# MAIN_SPACER_2.net
KiCad netlist of a schematic drawn in Altium Designer
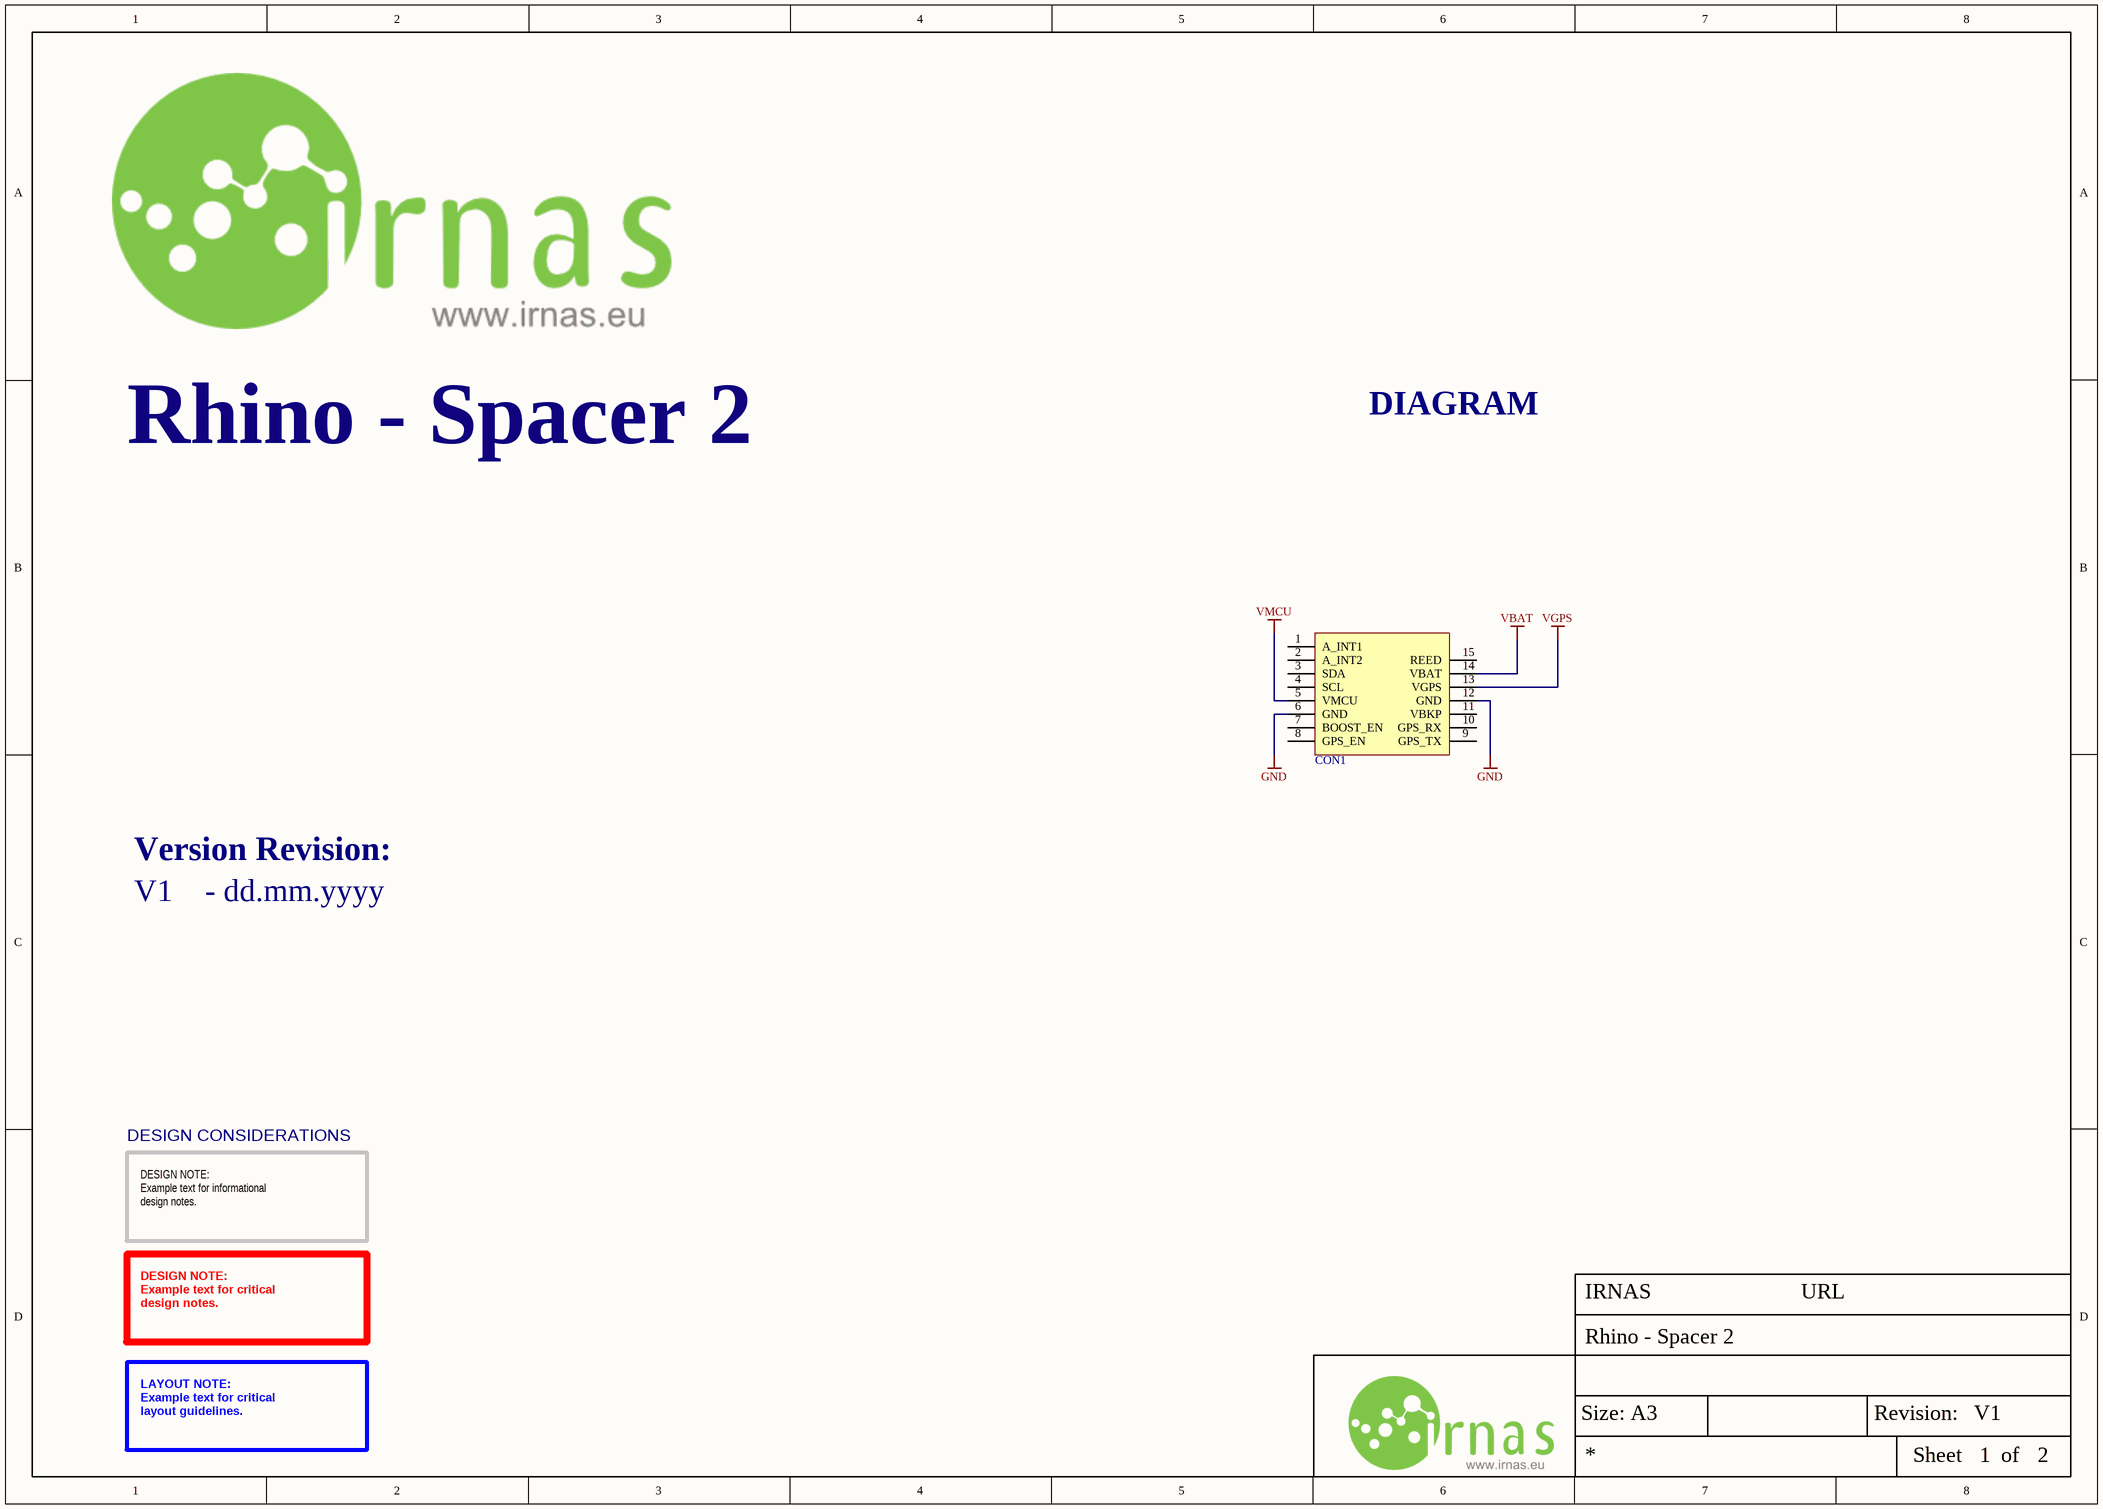
[diagram p0: MAIN_SPACER_2.SchDoc]

(export (version "E")
  (design (tool "Eeschema 10.0.6"))
  (components
    (comp (ref "CON1")
      (value "Between PCB connection")
      (footprint "SmartParks_Rhino")
      (libsource (lib "Connectors") (part "SmartParks_Rhino"))
    )
  )
  (nets
    (net (code "1") (name "GND") (class "Default")
      (node (ref "CON1") (pin "12") (pinfunction "GND_12") (pintype "passive"))
      (node (ref "CON1") (pin "6") (pinfunction "GND_6") (pintype "passive"))
    )
    (net (code "2") (name "VBAT") (class "Default")
      (node (ref "CON1") (pin "14") (pinfunction "VBAT_14") (pintype "passive"))
    )
    (net (code "3") (name "VGPS") (class "Default")
      (node (ref "CON1") (pin "13") (pinfunction "VGPS_13") (pintype "passive"))
    )
    (net (code "4") (name "VMCU") (class "Default")
      (node (ref "CON1") (pin "5") (pinfunction "VMCU_5") (pintype "passive"))
    )
    (net (code "5") (name "unconnected-(CON1-A_INT1-Pad1)") (class "Default")
      (node (ref "CON1") (pin "1") (pinfunction "A_INT1_1") (pintype "passive"))
    )
    (net (code "6") (name "unconnected-(CON1-A_INT2-Pad2)") (class "Default")
      (node (ref "CON1") (pin "2") (pinfunction "A_INT2_2") (pintype "passive"))
    )
    (net (code "7") (name "unconnected-(CON1-BOOST_EN-Pad7)") (class "Default")
      (node (ref "CON1") (pin "7") (pinfunction "BOOST_EN_7") (pintype "passive"))
    )
    (net (code "8") (name "unconnected-(CON1-GPS_EN-Pad8)") (class "Default")
      (node (ref "CON1") (pin "8") (pinfunction "GPS_EN_8") (pintype "passive"))
    )
    (net (code "9") (name "unconnected-(CON1-GPS_RX-Pad10)") (class "Default")
      (node (ref "CON1") (pin "10") (pinfunction "GPS_RX_10") (pintype "passive"))
    )
    (net (code "10") (name "unconnected-(CON1-GPS_TX-Pad9)") (class "Default")
      (node (ref "CON1") (pin "9") (pinfunction "GPS_TX_9") (pintype "passive"))
    )
    (net (code "11") (name "unconnected-(CON1-REED-Pad15)") (class "Default")
      (node (ref "CON1") (pin "15") (pinfunction "REED_15") (pintype "passive"))
    )
    (net (code "12") (name "unconnected-(CON1-SCL-Pad4)") (class "Default")
      (node (ref "CON1") (pin "4") (pinfunction "SCL_4") (pintype "passive"))
    )
    (net (code "13") (name "unconnected-(CON1-SDA-Pad3)") (class "Default")
      (node (ref "CON1") (pin "3") (pinfunction "SDA_3") (pintype "passive"))
    )
    (net (code "14") (name "unconnected-(CON1-VBKP-Pad11)") (class "Default")
      (node (ref "CON1") (pin "11") (pinfunction "VBKP_11") (pintype "passive"))
    )
  )
)
